# Pinduino-Nano-WPC-adaptor-panalized_2.net
KiCad netlist of a schematic drawn in EAGLE
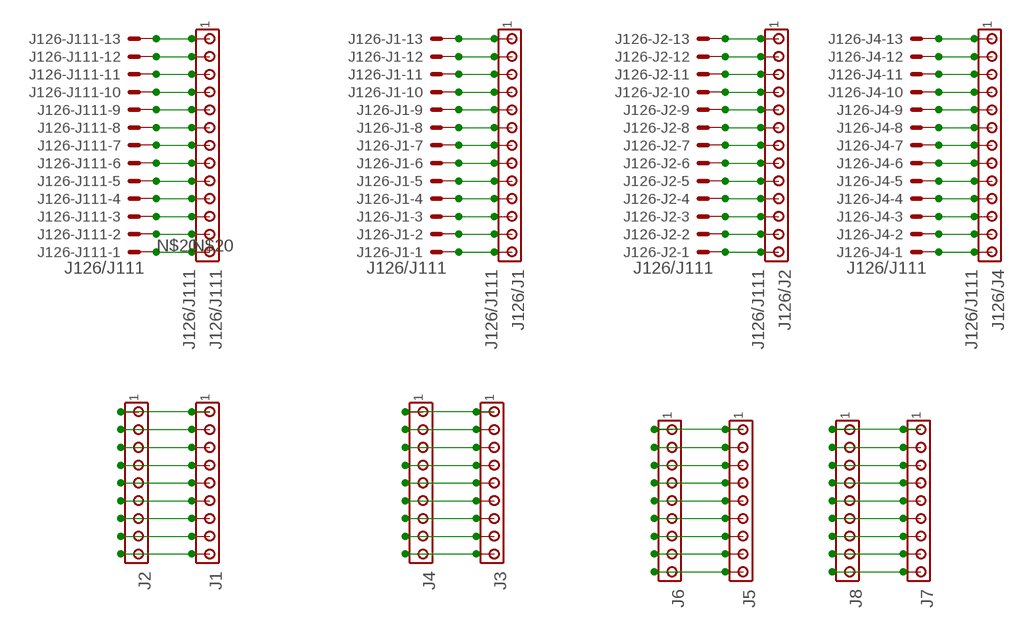
[diagram p0: schematic, sheet 1]

(export (version "E")
  (design (tool "Eeschema 10.0.6"))
  (components
    (comp (ref "J1")
      (value "MTA09-156")
      (footprint "eagle-import:1X9MTA")
      (libsource (lib "eagle-import") (part "MTA09-156"))
    )
    (comp (ref "J2")
      (value "MTA09-156")
      (footprint "eagle-import:1X9MTA")
      (libsource (lib "eagle-import") (part "MTA09-156"))
    )
    (comp (ref "J3")
      (value "MTA09-156")
      (footprint "eagle-import:1X9MTA")
      (libsource (lib "eagle-import") (part "MTA09-156"))
    )
    (comp (ref "J4")
      (value "MTA09-156")
      (footprint "eagle-import:1X9MTA")
      (libsource (lib "eagle-import") (part "MTA09-156"))
    )
    (comp (ref "J5")
      (value "MTA09-156")
      (footprint "eagle-import:1X9MTA")
      (libsource (lib "eagle-import") (part "MTA09-156"))
    )
    (comp (ref "J6")
      (value "MTA09-156")
      (footprint "eagle-import:1X9MTA")
      (libsource (lib "eagle-import") (part "MTA09-156"))
    )
    (comp (ref "J7")
      (value "MTA09-156")
      (footprint "eagle-import:1X9MTA")
      (libsource (lib "eagle-import") (part "MTA09-156"))
    )
    (comp (ref "J8")
      (value "MTA09-156")
      (footprint "eagle-import:1X9MTA")
      (libsource (lib "eagle-import") (part "MTA09-156"))
    )
    (comp (ref "J126-J1")
      (value "J126/J111")
      (footprint "eagle-import:KK-156-13")
      (libsource (lib "eagle-import") (part "KK-156-13"))
    )
    (comp (ref "J126-J2")
      (value "J126/J111")
      (footprint "eagle-import:KK-156-13")
      (libsource (lib "eagle-import") (part "KK-156-13"))
    )
    (comp (ref "J126-J4")
      (value "J126/J111")
      (footprint "eagle-import:KK-156-13")
      (libsource (lib "eagle-import") (part "KK-156-13"))
    )
    (comp (ref "J126-J111")
      (value "J126/J111")
      (footprint "eagle-import:KK-156-13")
      (libsource (lib "eagle-import") (part "KK-156-13"))
    )
    (comp (ref "J126/J1")
      (value "J126/J111")
      (footprint "eagle-import:1X13MTA")
      (libsource (lib "eagle-import") (part "MTA13-156"))
    )
    (comp (ref "J126/J2")
      (value "J126/J111")
      (footprint "eagle-import:1X13MTA")
      (libsource (lib "eagle-import") (part "MTA13-156"))
    )
    (comp (ref "J126/J4")
      (value "J126/J111")
      (footprint "eagle-import:1X13MTA")
      (libsource (lib "eagle-import") (part "MTA13-156"))
    )
    (comp (ref "J126/J111")
      (value "J126/J111")
      (footprint "eagle-import:1X13MTA")
      (libsource (lib "eagle-import") (part "MTA13-156"))
    )
  )
  (nets
    (net (code "1") (name "/N$20") (class "Default")
      (node (ref "J126-J111") (pin "2") (pinfunction "S_2") (pintype "passive"))
      (node (ref "J126/J111") (pin "12") (pinfunction "12_12") (pintype "passive"))
    )
    (net (code "2") (name "Net-(J1-Pad1)") (class "Default")
      (node (ref "J1") (pin "1") (pinfunction "1_1") (pintype "passive"))
      (node (ref "J2") (pin "1") (pinfunction "1_1") (pintype "passive"))
    )
    (net (code "3") (name "Net-(J1-Pad2)") (class "Default")
      (node (ref "J1") (pin "2") (pinfunction "2_2") (pintype "passive"))
      (node (ref "J2") (pin "2") (pinfunction "2_2") (pintype "passive"))
    )
    (net (code "4") (name "Net-(J1-Pad3)") (class "Default")
      (node (ref "J1") (pin "3") (pinfunction "3_3") (pintype "passive"))
      (node (ref "J2") (pin "3") (pinfunction "3_3") (pintype "passive"))
    )
    (net (code "5") (name "Net-(J1-Pad4)") (class "Default")
      (node (ref "J1") (pin "4") (pinfunction "4_4") (pintype "passive"))
      (node (ref "J2") (pin "4") (pinfunction "4_4") (pintype "passive"))
    )
    (net (code "6") (name "Net-(J1-Pad5)") (class "Default")
      (node (ref "J1") (pin "5") (pinfunction "5_5") (pintype "passive"))
      (node (ref "J2") (pin "5") (pinfunction "5_5") (pintype "passive"))
    )
    (net (code "7") (name "Net-(J1-Pad6)") (class "Default")
      (node (ref "J1") (pin "6") (pinfunction "6_6") (pintype "passive"))
      (node (ref "J2") (pin "6") (pinfunction "6_6") (pintype "passive"))
    )
    (net (code "8") (name "Net-(J1-Pad7)") (class "Default")
      (node (ref "J1") (pin "7") (pinfunction "7_7") (pintype "passive"))
      (node (ref "J2") (pin "7") (pinfunction "7_7") (pintype "passive"))
    )
    (net (code "9") (name "Net-(J1-Pad8)") (class "Default")
      (node (ref "J1") (pin "8") (pinfunction "8_8") (pintype "passive"))
      (node (ref "J2") (pin "8") (pinfunction "8_8") (pintype "passive"))
    )
    (net (code "10") (name "Net-(J1-Pad9)") (class "Default")
      (node (ref "J1") (pin "9") (pinfunction "9_9") (pintype "passive"))
      (node (ref "J2") (pin "9") (pinfunction "9_9") (pintype "passive"))
    )
    (net (code "11") (name "Net-(J3-Pad1)") (class "Default")
      (node (ref "J3") (pin "1") (pinfunction "1_1") (pintype "passive"))
      (node (ref "J4") (pin "1") (pinfunction "1_1") (pintype "passive"))
    )
    (net (code "12") (name "Net-(J3-Pad2)") (class "Default")
      (node (ref "J3") (pin "2") (pinfunction "2_2") (pintype "passive"))
      (node (ref "J4") (pin "2") (pinfunction "2_2") (pintype "passive"))
    )
    (net (code "13") (name "Net-(J3-Pad3)") (class "Default")
      (node (ref "J3") (pin "3") (pinfunction "3_3") (pintype "passive"))
      (node (ref "J4") (pin "3") (pinfunction "3_3") (pintype "passive"))
    )
    (net (code "14") (name "Net-(J3-Pad4)") (class "Default")
      (node (ref "J3") (pin "4") (pinfunction "4_4") (pintype "passive"))
      (node (ref "J4") (pin "4") (pinfunction "4_4") (pintype "passive"))
    )
    (net (code "15") (name "Net-(J3-Pad5)") (class "Default")
      (node (ref "J3") (pin "5") (pinfunction "5_5") (pintype "passive"))
      (node (ref "J4") (pin "5") (pinfunction "5_5") (pintype "passive"))
    )
    (net (code "16") (name "Net-(J3-Pad6)") (class "Default")
      (node (ref "J3") (pin "6") (pinfunction "6_6") (pintype "passive"))
      (node (ref "J4") (pin "6") (pinfunction "6_6") (pintype "passive"))
    )
    (net (code "17") (name "Net-(J3-Pad7)") (class "Default")
      (node (ref "J3") (pin "7") (pinfunction "7_7") (pintype "passive"))
      (node (ref "J4") (pin "7") (pinfunction "7_7") (pintype "passive"))
    )
    (net (code "18") (name "Net-(J3-Pad8)") (class "Default")
      (node (ref "J3") (pin "8") (pinfunction "8_8") (pintype "passive"))
      (node (ref "J4") (pin "8") (pinfunction "8_8") (pintype "passive"))
    )
    (net (code "19") (name "Net-(J3-Pad9)") (class "Default")
      (node (ref "J3") (pin "9") (pinfunction "9_9") (pintype "passive"))
      (node (ref "J4") (pin "9") (pinfunction "9_9") (pintype "passive"))
    )
    (net (code "20") (name "Net-(J5-Pad1)") (class "Default")
      (node (ref "J5") (pin "1") (pinfunction "1_1") (pintype "passive"))
      (node (ref "J6") (pin "1") (pinfunction "1_1") (pintype "passive"))
    )
    (net (code "21") (name "Net-(J5-Pad2)") (class "Default")
      (node (ref "J5") (pin "2") (pinfunction "2_2") (pintype "passive"))
      (node (ref "J6") (pin "2") (pinfunction "2_2") (pintype "passive"))
    )
    (net (code "22") (name "Net-(J5-Pad3)") (class "Default")
      (node (ref "J5") (pin "3") (pinfunction "3_3") (pintype "passive"))
      (node (ref "J6") (pin "3") (pinfunction "3_3") (pintype "passive"))
    )
    (net (code "23") (name "Net-(J5-Pad4)") (class "Default")
      (node (ref "J5") (pin "4") (pinfunction "4_4") (pintype "passive"))
      (node (ref "J6") (pin "4") (pinfunction "4_4") (pintype "passive"))
    )
    (net (code "24") (name "Net-(J5-Pad5)") (class "Default")
      (node (ref "J5") (pin "5") (pinfunction "5_5") (pintype "passive"))
      (node (ref "J6") (pin "5") (pinfunction "5_5") (pintype "passive"))
    )
    (net (code "25") (name "Net-(J5-Pad6)") (class "Default")
      (node (ref "J5") (pin "6") (pinfunction "6_6") (pintype "passive"))
      (node (ref "J6") (pin "6") (pinfunction "6_6") (pintype "passive"))
    )
    (net (code "26") (name "Net-(J5-Pad7)") (class "Default")
      (node (ref "J5") (pin "7") (pinfunction "7_7") (pintype "passive"))
      (node (ref "J6") (pin "7") (pinfunction "7_7") (pintype "passive"))
    )
    (net (code "27") (name "Net-(J5-Pad8)") (class "Default")
      (node (ref "J5") (pin "8") (pinfunction "8_8") (pintype "passive"))
      (node (ref "J6") (pin "8") (pinfunction "8_8") (pintype "passive"))
    )
    (net (code "28") (name "Net-(J5-Pad9)") (class "Default")
      (node (ref "J5") (pin "9") (pinfunction "9_9") (pintype "passive"))
      (node (ref "J6") (pin "9") (pinfunction "9_9") (pintype "passive"))
    )
    (net (code "29") (name "Net-(J7-Pad1)") (class "Default")
      (node (ref "J7") (pin "1") (pinfunction "1_1") (pintype "passive"))
      (node (ref "J8") (pin "1") (pinfunction "1_1") (pintype "passive"))
    )
    (net (code "30") (name "Net-(J7-Pad2)") (class "Default")
      (node (ref "J7") (pin "2") (pinfunction "2_2") (pintype "passive"))
      (node (ref "J8") (pin "2") (pinfunction "2_2") (pintype "passive"))
    )
    (net (code "31") (name "Net-(J7-Pad3)") (class "Default")
      (node (ref "J7") (pin "3") (pinfunction "3_3") (pintype "passive"))
      (node (ref "J8") (pin "3") (pinfunction "3_3") (pintype "passive"))
    )
    (net (code "32") (name "Net-(J7-Pad4)") (class "Default")
      (node (ref "J7") (pin "4") (pinfunction "4_4") (pintype "passive"))
      (node (ref "J8") (pin "4") (pinfunction "4_4") (pintype "passive"))
    )
    (net (code "33") (name "Net-(J7-Pad5)") (class "Default")
      (node (ref "J7") (pin "5") (pinfunction "5_5") (pintype "passive"))
      (node (ref "J8") (pin "5") (pinfunction "5_5") (pintype "passive"))
    )
    (net (code "34") (name "Net-(J7-Pad6)") (class "Default")
      (node (ref "J7") (pin "6") (pinfunction "6_6") (pintype "passive"))
      (node (ref "J8") (pin "6") (pinfunction "6_6") (pintype "passive"))
    )
    (net (code "35") (name "Net-(J7-Pad7)") (class "Default")
      (node (ref "J7") (pin "7") (pinfunction "7_7") (pintype "passive"))
      (node (ref "J8") (pin "7") (pinfunction "7_7") (pintype "passive"))
    )
    (net (code "36") (name "Net-(J7-Pad8)") (class "Default")
      (node (ref "J7") (pin "8") (pinfunction "8_8") (pintype "passive"))
      (node (ref "J8") (pin "8") (pinfunction "8_8") (pintype "passive"))
    )
    (net (code "37") (name "Net-(J7-Pad9)") (class "Default")
      (node (ref "J7") (pin "9") (pinfunction "9_9") (pintype "passive"))
      (node (ref "J8") (pin "9") (pinfunction "9_9") (pintype "passive"))
    )
    (net (code "38") (name "Net-(J126-J1A-S)") (class "Default")
      (node (ref "J126-J1") (pin "1") (pinfunction "S_1") (pintype "passive"))
      (node (ref "J126/J1") (pin "13") (pinfunction "13_13") (pintype "passive"))
    )
    (net (code "39") (name "Net-(J126-J1B-S)") (class "Default")
      (node (ref "J126-J1") (pin "10") (pinfunction "S_10") (pintype "passive"))
      (node (ref "J126/J1") (pin "4") (pinfunction "4_4") (pintype "passive"))
    )
    (net (code "40") (name "Net-(J126-J1C-S)") (class "Default")
      (node (ref "J126-J1") (pin "11") (pinfunction "S_11") (pintype "passive"))
      (node (ref "J126/J1") (pin "3") (pinfunction "3_3") (pintype "passive"))
    )
    (net (code "41") (name "Net-(J126-J1D-S)") (class "Default")
      (node (ref "J126-J1") (pin "12") (pinfunction "S_12") (pintype "passive"))
      (node (ref "J126/J1") (pin "2") (pinfunction "2_2") (pintype "passive"))
    )
    (net (code "42") (name "Net-(J126-J1E-S)") (class "Default")
      (node (ref "J126-J1") (pin "13") (pinfunction "S_13") (pintype "passive"))
      (node (ref "J126/J1") (pin "1") (pinfunction "1_1") (pintype "passive"))
    )
    (net (code "43") (name "Net-(J126-J1F-S)") (class "Default")
      (node (ref "J126-J1") (pin "2") (pinfunction "S_2") (pintype "passive"))
      (node (ref "J126/J1") (pin "12") (pinfunction "12_12") (pintype "passive"))
    )
    (net (code "44") (name "Net-(J126-J1G-S)") (class "Default")
      (node (ref "J126-J1") (pin "3") (pinfunction "S_3") (pintype "passive"))
      (node (ref "J126/J1") (pin "11") (pinfunction "11_11") (pintype "passive"))
    )
    (net (code "45") (name "Net-(J126-J1H-S)") (class "Default")
      (node (ref "J126-J1") (pin "4") (pinfunction "S_4") (pintype "passive"))
      (node (ref "J126/J1") (pin "10") (pinfunction "10_10") (pintype "passive"))
    )
    (net (code "46") (name "Net-(J126-J1I-S)") (class "Default")
      (node (ref "J126-J1") (pin "5") (pinfunction "S_5") (pintype "passive"))
      (node (ref "J126/J1") (pin "9") (pinfunction "9_9") (pintype "passive"))
    )
    (net (code "47") (name "Net-(J126-J1J-S)") (class "Default")
      (node (ref "J126-J1") (pin "6") (pinfunction "S_6") (pintype "passive"))
      (node (ref "J126/J1") (pin "8") (pinfunction "8_8") (pintype "passive"))
    )
    (net (code "48") (name "Net-(J126-J1K-S)") (class "Default")
      (node (ref "J126-J1") (pin "7") (pinfunction "S_7") (pintype "passive"))
      (node (ref "J126/J1") (pin "7") (pinfunction "7_7") (pintype "passive"))
    )
    (net (code "49") (name "Net-(J126-J1L-S)") (class "Default")
      (node (ref "J126-J1") (pin "8") (pinfunction "S_8") (pintype "passive"))
      (node (ref "J126/J1") (pin "6") (pinfunction "6_6") (pintype "passive"))
    )
    (net (code "50") (name "Net-(J126-J1M-S)") (class "Default")
      (node (ref "J126-J1") (pin "9") (pinfunction "S_9") (pintype "passive"))
      (node (ref "J126/J1") (pin "5") (pinfunction "5_5") (pintype "passive"))
    )
    (net (code "51") (name "Net-(J126-J2A-S)") (class "Default")
      (node (ref "J126-J2") (pin "1") (pinfunction "S_1") (pintype "passive"))
      (node (ref "J126/J2") (pin "13") (pinfunction "13_13") (pintype "passive"))
    )
    (net (code "52") (name "Net-(J126-J2B-S)") (class "Default")
      (node (ref "J126-J2") (pin "10") (pinfunction "S_10") (pintype "passive"))
      (node (ref "J126/J2") (pin "4") (pinfunction "4_4") (pintype "passive"))
    )
    (net (code "53") (name "Net-(J126-J2C-S)") (class "Default")
      (node (ref "J126-J2") (pin "11") (pinfunction "S_11") (pintype "passive"))
      (node (ref "J126/J2") (pin "3") (pinfunction "3_3") (pintype "passive"))
    )
    (net (code "54") (name "Net-(J126-J2D-S)") (class "Default")
      (node (ref "J126-J2") (pin "12") (pinfunction "S_12") (pintype "passive"))
      (node (ref "J126/J2") (pin "2") (pinfunction "2_2") (pintype "passive"))
    )
    (net (code "55") (name "Net-(J126-J2E-S)") (class "Default")
      (node (ref "J126-J2") (pin "13") (pinfunction "S_13") (pintype "passive"))
      (node (ref "J126/J2") (pin "1") (pinfunction "1_1") (pintype "passive"))
    )
    (net (code "56") (name "Net-(J126-J2F-S)") (class "Default")
      (node (ref "J126-J2") (pin "2") (pinfunction "S_2") (pintype "passive"))
      (node (ref "J126/J2") (pin "12") (pinfunction "12_12") (pintype "passive"))
    )
    (net (code "57") (name "Net-(J126-J2G-S)") (class "Default")
      (node (ref "J126-J2") (pin "3") (pinfunction "S_3") (pintype "passive"))
      (node (ref "J126/J2") (pin "11") (pinfunction "11_11") (pintype "passive"))
    )
    (net (code "58") (name "Net-(J126-J2H-S)") (class "Default")
      (node (ref "J126-J2") (pin "4") (pinfunction "S_4") (pintype "passive"))
      (node (ref "J126/J2") (pin "10") (pinfunction "10_10") (pintype "passive"))
    )
    (net (code "59") (name "Net-(J126-J2I-S)") (class "Default")
      (node (ref "J126-J2") (pin "5") (pinfunction "S_5") (pintype "passive"))
      (node (ref "J126/J2") (pin "9") (pinfunction "9_9") (pintype "passive"))
    )
    (net (code "60") (name "Net-(J126-J2J-S)") (class "Default")
      (node (ref "J126-J2") (pin "6") (pinfunction "S_6") (pintype "passive"))
      (node (ref "J126/J2") (pin "8") (pinfunction "8_8") (pintype "passive"))
    )
    (net (code "61") (name "Net-(J126-J2K-S)") (class "Default")
      (node (ref "J126-J2") (pin "7") (pinfunction "S_7") (pintype "passive"))
      (node (ref "J126/J2") (pin "7") (pinfunction "7_7") (pintype "passive"))
    )
    (net (code "62") (name "Net-(J126-J2L-S)") (class "Default")
      (node (ref "J126-J2") (pin "8") (pinfunction "S_8") (pintype "passive"))
      (node (ref "J126/J2") (pin "6") (pinfunction "6_6") (pintype "passive"))
    )
    (net (code "63") (name "Net-(J126-J2M-S)") (class "Default")
      (node (ref "J126-J2") (pin "9") (pinfunction "S_9") (pintype "passive"))
      (node (ref "J126/J2") (pin "5") (pinfunction "5_5") (pintype "passive"))
    )
    (net (code "64") (name "Net-(J126-J4A-S)") (class "Default")
      (node (ref "J126-J4") (pin "1") (pinfunction "S_1") (pintype "passive"))
      (node (ref "J126/J4") (pin "13") (pinfunction "13_13") (pintype "passive"))
    )
    (net (code "65") (name "Net-(J126-J4B-S)") (class "Default")
      (node (ref "J126-J4") (pin "10") (pinfunction "S_10") (pintype "passive"))
      (node (ref "J126/J4") (pin "4") (pinfunction "4_4") (pintype "passive"))
    )
    (net (code "66") (name "Net-(J126-J4C-S)") (class "Default")
      (node (ref "J126-J4") (pin "11") (pinfunction "S_11") (pintype "passive"))
      (node (ref "J126/J4") (pin "3") (pinfunction "3_3") (pintype "passive"))
    )
    (net (code "67") (name "Net-(J126-J4D-S)") (class "Default")
      (node (ref "J126-J4") (pin "12") (pinfunction "S_12") (pintype "passive"))
      (node (ref "J126/J4") (pin "2") (pinfunction "2_2") (pintype "passive"))
    )
    (net (code "68") (name "Net-(J126-J4E-S)") (class "Default")
      (node (ref "J126-J4") (pin "13") (pinfunction "S_13") (pintype "passive"))
      (node (ref "J126/J4") (pin "1") (pinfunction "1_1") (pintype "passive"))
    )
    (net (code "69") (name "Net-(J126-J4F-S)") (class "Default")
      (node (ref "J126-J4") (pin "2") (pinfunction "S_2") (pintype "passive"))
      (node (ref "J126/J4") (pin "12") (pinfunction "12_12") (pintype "passive"))
    )
    (net (code "70") (name "Net-(J126-J4G-S)") (class "Default")
      (node (ref "J126-J4") (pin "3") (pinfunction "S_3") (pintype "passive"))
      (node (ref "J126/J4") (pin "11") (pinfunction "11_11") (pintype "passive"))
    )
    (net (code "71") (name "Net-(J126-J4H-S)") (class "Default")
      (node (ref "J126-J4") (pin "4") (pinfunction "S_4") (pintype "passive"))
      (node (ref "J126/J4") (pin "10") (pinfunction "10_10") (pintype "passive"))
    )
    (net (code "72") (name "Net-(J126-J4I-S)") (class "Default")
      (node (ref "J126-J4") (pin "5") (pinfunction "S_5") (pintype "passive"))
      (node (ref "J126/J4") (pin "9") (pinfunction "9_9") (pintype "passive"))
    )
    (net (code "73") (name "Net-(J126-J4J-S)") (class "Default")
      (node (ref "J126-J4") (pin "6") (pinfunction "S_6") (pintype "passive"))
      (node (ref "J126/J4") (pin "8") (pinfunction "8_8") (pintype "passive"))
    )
    (net (code "74") (name "Net-(J126-J4K-S)") (class "Default")
      (node (ref "J126-J4") (pin "7") (pinfunction "S_7") (pintype "passive"))
      (node (ref "J126/J4") (pin "7") (pinfunction "7_7") (pintype "passive"))
    )
    (net (code "75") (name "Net-(J126-J4L-S)") (class "Default")
      (node (ref "J126-J4") (pin "8") (pinfunction "S_8") (pintype "passive"))
      (node (ref "J126/J4") (pin "6") (pinfunction "6_6") (pintype "passive"))
    )
    (net (code "76") (name "Net-(J126-J4M-S)") (class "Default")
      (node (ref "J126-J4") (pin "9") (pinfunction "S_9") (pintype "passive"))
      (node (ref "J126/J4") (pin "5") (pinfunction "5_5") (pintype "passive"))
    )
    (net (code "77") (name "Net-(J126-J111A-S)") (class "Default")
      (node (ref "J126-J111") (pin "1") (pinfunction "S_1") (pintype "passive"))
      (node (ref "J126/J111") (pin "13") (pinfunction "13_13") (pintype "passive"))
    )
    (net (code "78") (name "Net-(J126-J111B-S)") (class "Default")
      (node (ref "J126-J111") (pin "10") (pinfunction "S_10") (pintype "passive"))
      (node (ref "J126/J111") (pin "4") (pinfunction "4_4") (pintype "passive"))
    )
    (net (code "79") (name "Net-(J126-J111C-S)") (class "Default")
      (node (ref "J126-J111") (pin "11") (pinfunction "S_11") (pintype "passive"))
      (node (ref "J126/J111") (pin "3") (pinfunction "3_3") (pintype "passive"))
    )
    (net (code "80") (name "Net-(J126-J111D-S)") (class "Default")
      (node (ref "J126-J111") (pin "12") (pinfunction "S_12") (pintype "passive"))
      (node (ref "J126/J111") (pin "2") (pinfunction "2_2") (pintype "passive"))
    )
    (net (code "81") (name "Net-(J126-J111E-S)") (class "Default")
      (node (ref "J126-J111") (pin "13") (pinfunction "S_13") (pintype "passive"))
      (node (ref "J126/J111") (pin "1") (pinfunction "1_1") (pintype "passive"))
    )
    (net (code "82") (name "Net-(J126-J111G-S)") (class "Default")
      (node (ref "J126-J111") (pin "3") (pinfunction "S_3") (pintype "passive"))
      (node (ref "J126/J111") (pin "11") (pinfunction "11_11") (pintype "passive"))
    )
    (net (code "83") (name "Net-(J126-J111H-S)") (class "Default")
      (node (ref "J126-J111") (pin "4") (pinfunction "S_4") (pintype "passive"))
      (node (ref "J126/J111") (pin "10") (pinfunction "10_10") (pintype "passive"))
    )
    (net (code "84") (name "Net-(J126-J111I-S)") (class "Default")
      (node (ref "J126-J111") (pin "5") (pinfunction "S_5") (pintype "passive"))
      (node (ref "J126/J111") (pin "9") (pinfunction "9_9") (pintype "passive"))
    )
    (net (code "85") (name "Net-(J126-J111J-S)") (class "Default")
      (node (ref "J126-J111") (pin "6") (pinfunction "S_6") (pintype "passive"))
      (node (ref "J126/J111") (pin "8") (pinfunction "8_8") (pintype "passive"))
    )
    (net (code "86") (name "Net-(J126-J111K-S)") (class "Default")
      (node (ref "J126-J111") (pin "7") (pinfunction "S_7") (pintype "passive"))
      (node (ref "J126/J111") (pin "7") (pinfunction "7_7") (pintype "passive"))
    )
    (net (code "87") (name "Net-(J126-J111L-S)") (class "Default")
      (node (ref "J126-J111") (pin "8") (pinfunction "S_8") (pintype "passive"))
      (node (ref "J126/J111") (pin "6") (pinfunction "6_6") (pintype "passive"))
    )
    (net (code "88") (name "Net-(J126-J111M-S)") (class "Default")
      (node (ref "J126-J111") (pin "9") (pinfunction "S_9") (pintype "passive"))
      (node (ref "J126/J111") (pin "5") (pinfunction "5_5") (pintype "passive"))
    )
  )
)
